# TPS54331_2A.net
KiCad netlist of a schematic drawn in Altium Designer
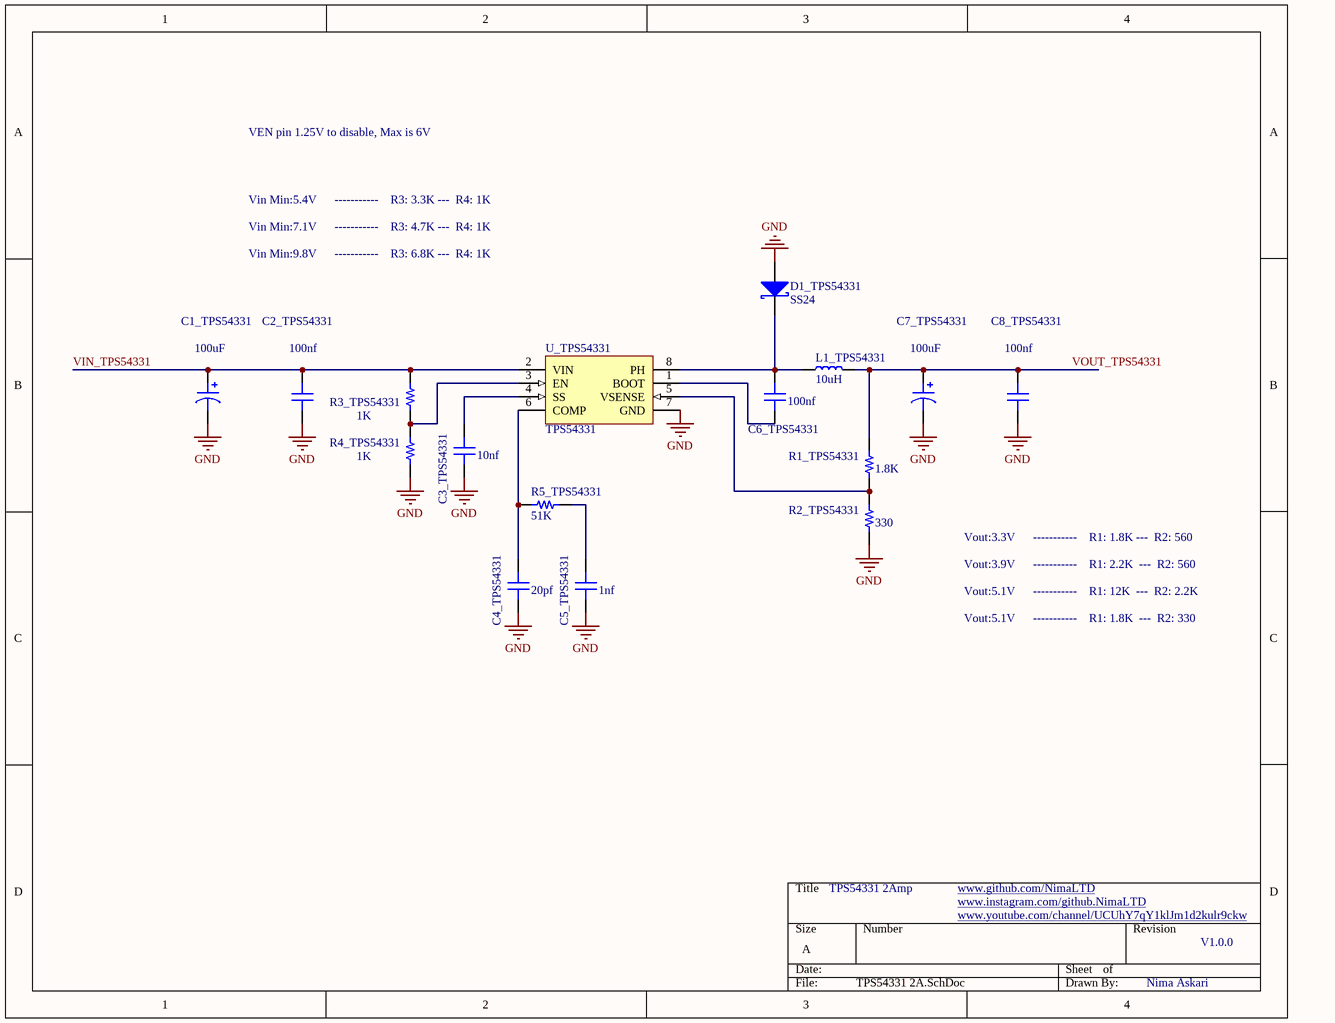
[diagram p0: TPS54331 2A.SchDoc]

(export (version "E")
  (design (tool "Eeschema 10.0.6"))
  (components
    (comp (ref "C1_TPS54331")
      (value "100uF")
      (footprint "CAP AL SMD D6 H6")
      (description "SMT Polarised Capacitor")
      (libsource (lib "CAPACITOR") (part "Pol Cap SMD AL D6 H6"))
    )
    (comp (ref "C2_TPS54331")
      (value "100nf")
      (footprint "CAP 1206")
      (description "SMT Capacitor")
      (libsource (lib "CAPACITOR") (part "Cap SMD 1206"))
    )
    (comp (ref "C3_TPS54331")
      (value "10nf")
      (footprint "CAP 0805")
      (description "SMT Capacitor")
      (libsource (lib "CAPACITOR") (part "Cap SMD 0805"))
    )
    (comp (ref "C4_TPS54331")
      (value "20pf")
      (footprint "CAP 0805")
      (description "SMT Capacitor")
      (libsource (lib "CAPACITOR") (part "Cap SMD 0805"))
    )
    (comp (ref "C5_TPS54331")
      (value "1nf")
      (footprint "CAP 0805")
      (description "SMT Capacitor")
      (libsource (lib "CAPACITOR") (part "Cap SMD 0805"))
    )
    (comp (ref "C6_TPS54331")
      (value "100nf")
      (footprint "CAP 0805")
      (description "SMT Capacitor")
      (libsource (lib "CAPACITOR") (part "Cap SMD 0805"))
    )
    (comp (ref "C7_TPS54331")
      (value "100uF")
      (footprint "CAP AL SMD D6 H6")
      (description "SMT Polarised Capacitor")
      (libsource (lib "CAPACITOR") (part "Pol Cap SMD AL D6 H6"))
    )
    (comp (ref "C8_TPS54331")
      (value "100nf")
      (footprint "CAP 0805")
      (description "SMT Capacitor")
      (libsource (lib "CAPACITOR") (part "Cap SMD 0805"))
    )
    (comp (ref "D1_TPS54331")
      (value "SS24 SMD")
      (footprint "DO214AA SMB")
      (description "2A Schottky")
      (fields (field (name "PARAMETER 1") "SS24"))
      (libsource (lib "DIODE") (part "SS24 SMD"))
    )
    (comp (ref "L1_TPS54331")
      (value "10uH")
      (footprint "IND 10X11")
      (description "SMT Inductor")
      (fields (field (name "Comment") "Inductor SMD POWER 10X11mm"))
      (libsource (lib "INDUCTOR") (part "Inductor SMD POWER 10X11mm"))
    )
    (comp (ref "R1_TPS54331")
      (value "1.8K")
      (footprint "RES 0805")
      (description "SMD Resistor")
      (libsource (lib "RESISTOR") (part "Res SMD 0805"))
    )
    (comp (ref "R2_TPS54331")
      (value "330")
      (footprint "RES 0805")
      (description "SMD Resistor")
      (libsource (lib "RESISTOR") (part "Res SMD 0805"))
    )
    (comp (ref "R3_TPS54331")
      (value "1K")
      (footprint "RES 0805")
      (description "SMD Resistor")
      (libsource (lib "RESISTOR") (part "Res SMD 0805"))
    )
    (comp (ref "R4_TPS54331")
      (value "1K")
      (footprint "RES 0805")
      (description "SMD Resistor")
      (libsource (lib "RESISTOR") (part "Res SMD 0805"))
    )
    (comp (ref "R5_TPS54331")
      (value "51K")
      (footprint "RES 0805")
      (description "SMD Resistor")
      (libsource (lib "RESISTOR") (part "Res SMD 0805"))
    )
    (comp (ref "U_TPS54331")
      (value "TPS54331")
      (footprint "SOP8")
      (fields (field (name "PARTNUMBER") "TPS54331"))
      (libsource (lib "IC") (part "TPS54331"))
    )
  )
  (nets
    (net (code "1") (name "/VIN_TPS54331") (class "Default")
      (node (ref "C1_TPS54331") (pin "1") (pinfunction "1_1") (pintype "passive"))
      (node (ref "C2_TPS54331") (pin "2") (pinfunction "2_2") (pintype "passive"))
      (node (ref "R3_TPS54331") (pin "2") (pinfunction "2_2") (pintype "passive"))
      (node (ref "U_TPS54331") (pin "2") (pinfunction "VIN_2") (pintype "power_in"))
    )
    (net (code "2") (name "/VOUT_TPS54331") (class "Default")
      (node (ref "C7_TPS54331") (pin "1") (pinfunction "1_1") (pintype "passive"))
      (node (ref "C8_TPS54331") (pin "2") (pinfunction "2_2") (pintype "passive"))
      (node (ref "L1_TPS54331") (pin "2") (pinfunction "2_2") (pintype "passive"))
      (node (ref "R1_TPS54331") (pin "2") (pinfunction "2_2") (pintype "passive"))
    )
    (net (code "3") (name "GND") (class "Default")
      (node (ref "C1_TPS54331") (pin "2") (pinfunction "2_2") (pintype "passive"))
      (node (ref "C2_TPS54331") (pin "1") (pinfunction "1_1") (pintype "passive"))
      (node (ref "C3_TPS54331") (pin "1") (pinfunction "1_1") (pintype "passive"))
      (node (ref "C4_TPS54331") (pin "1") (pinfunction "1_1") (pintype "passive"))
      (node (ref "C5_TPS54331") (pin "1") (pinfunction "1_1") (pintype "passive"))
      (node (ref "C7_TPS54331") (pin "2") (pinfunction "2_2") (pintype "passive"))
      (node (ref "C8_TPS54331") (pin "1") (pinfunction "1_1") (pintype "passive"))
      (node (ref "D1_TPS54331") (pin "1") (pinfunction "A_1") (pintype "passive"))
      (node (ref "R2_TPS54331") (pin "1") (pinfunction "1_1") (pintype "passive"))
      (node (ref "R4_TPS54331") (pin "1") (pinfunction "1_1") (pintype "passive"))
      (node (ref "U_TPS54331") (pin "7") (pinfunction "GND_7") (pintype "power_in"))
    )
    (net (code "4") (name "Net-(C5_TPS54331-Pad2)") (class "Default")
      (node (ref "C5_TPS54331") (pin "2") (pinfunction "2_2") (pintype "passive"))
      (node (ref "R5_TPS54331") (pin "1") (pinfunction "1_1") (pintype "passive"))
    )
    (net (code "5") (name "Net-(D1_TPS54331-K)") (class "Default")
      (node (ref "C6_TPS54331") (pin "2") (pinfunction "2_2") (pintype "passive"))
      (node (ref "D1_TPS54331") (pin "2") (pinfunction "K_2") (pintype "passive"))
      (node (ref "L1_TPS54331") (pin "1") (pinfunction "1_1") (pintype "passive"))
      (node (ref "U_TPS54331") (pin "8") (pinfunction "PH_8") (pintype "power_in"))
    )
    (net (code "6") (name "Net-(U_TPS54331-BOOT)") (class "Default")
      (node (ref "C6_TPS54331") (pin "1") (pinfunction "1_1") (pintype "passive"))
      (node (ref "U_TPS54331") (pin "1") (pinfunction "BOOT_1") (pintype "passive"))
    )
    (net (code "7") (name "Net-(U_TPS54331-COMP)") (class "Default")
      (node (ref "C4_TPS54331") (pin "2") (pinfunction "2_2") (pintype "passive"))
      (node (ref "R5_TPS54331") (pin "2") (pinfunction "2_2") (pintype "passive"))
      (node (ref "U_TPS54331") (pin "6") (pinfunction "COMP_6") (pintype "passive"))
    )
    (net (code "8") (name "Net-(U_TPS54331-EN)") (class "Default")
      (node (ref "R3_TPS54331") (pin "1") (pinfunction "1_1") (pintype "passive"))
      (node (ref "R4_TPS54331") (pin "2") (pinfunction "2_2") (pintype "passive"))
      (node (ref "U_TPS54331") (pin "3") (pinfunction "EN_3") (pintype "input"))
    )
    (net (code "9") (name "Net-(U_TPS54331-SS)") (class "Default")
      (node (ref "C3_TPS54331") (pin "2") (pinfunction "2_2") (pintype "passive"))
      (node (ref "U_TPS54331") (pin "4") (pinfunction "SS_4") (pintype "input"))
    )
    (net (code "10") (name "Net-(U_TPS54331-VSENSE)") (class "Default")
      (node (ref "R1_TPS54331") (pin "1") (pinfunction "1_1") (pintype "passive"))
      (node (ref "R2_TPS54331") (pin "2") (pinfunction "2_2") (pintype "passive"))
      (node (ref "U_TPS54331") (pin "5") (pinfunction "VSENSE_5") (pintype "input"))
    )
  )
)
